# Utility_Micro_v81.net
KiCad netlist of a schematic drawn in EAGLE
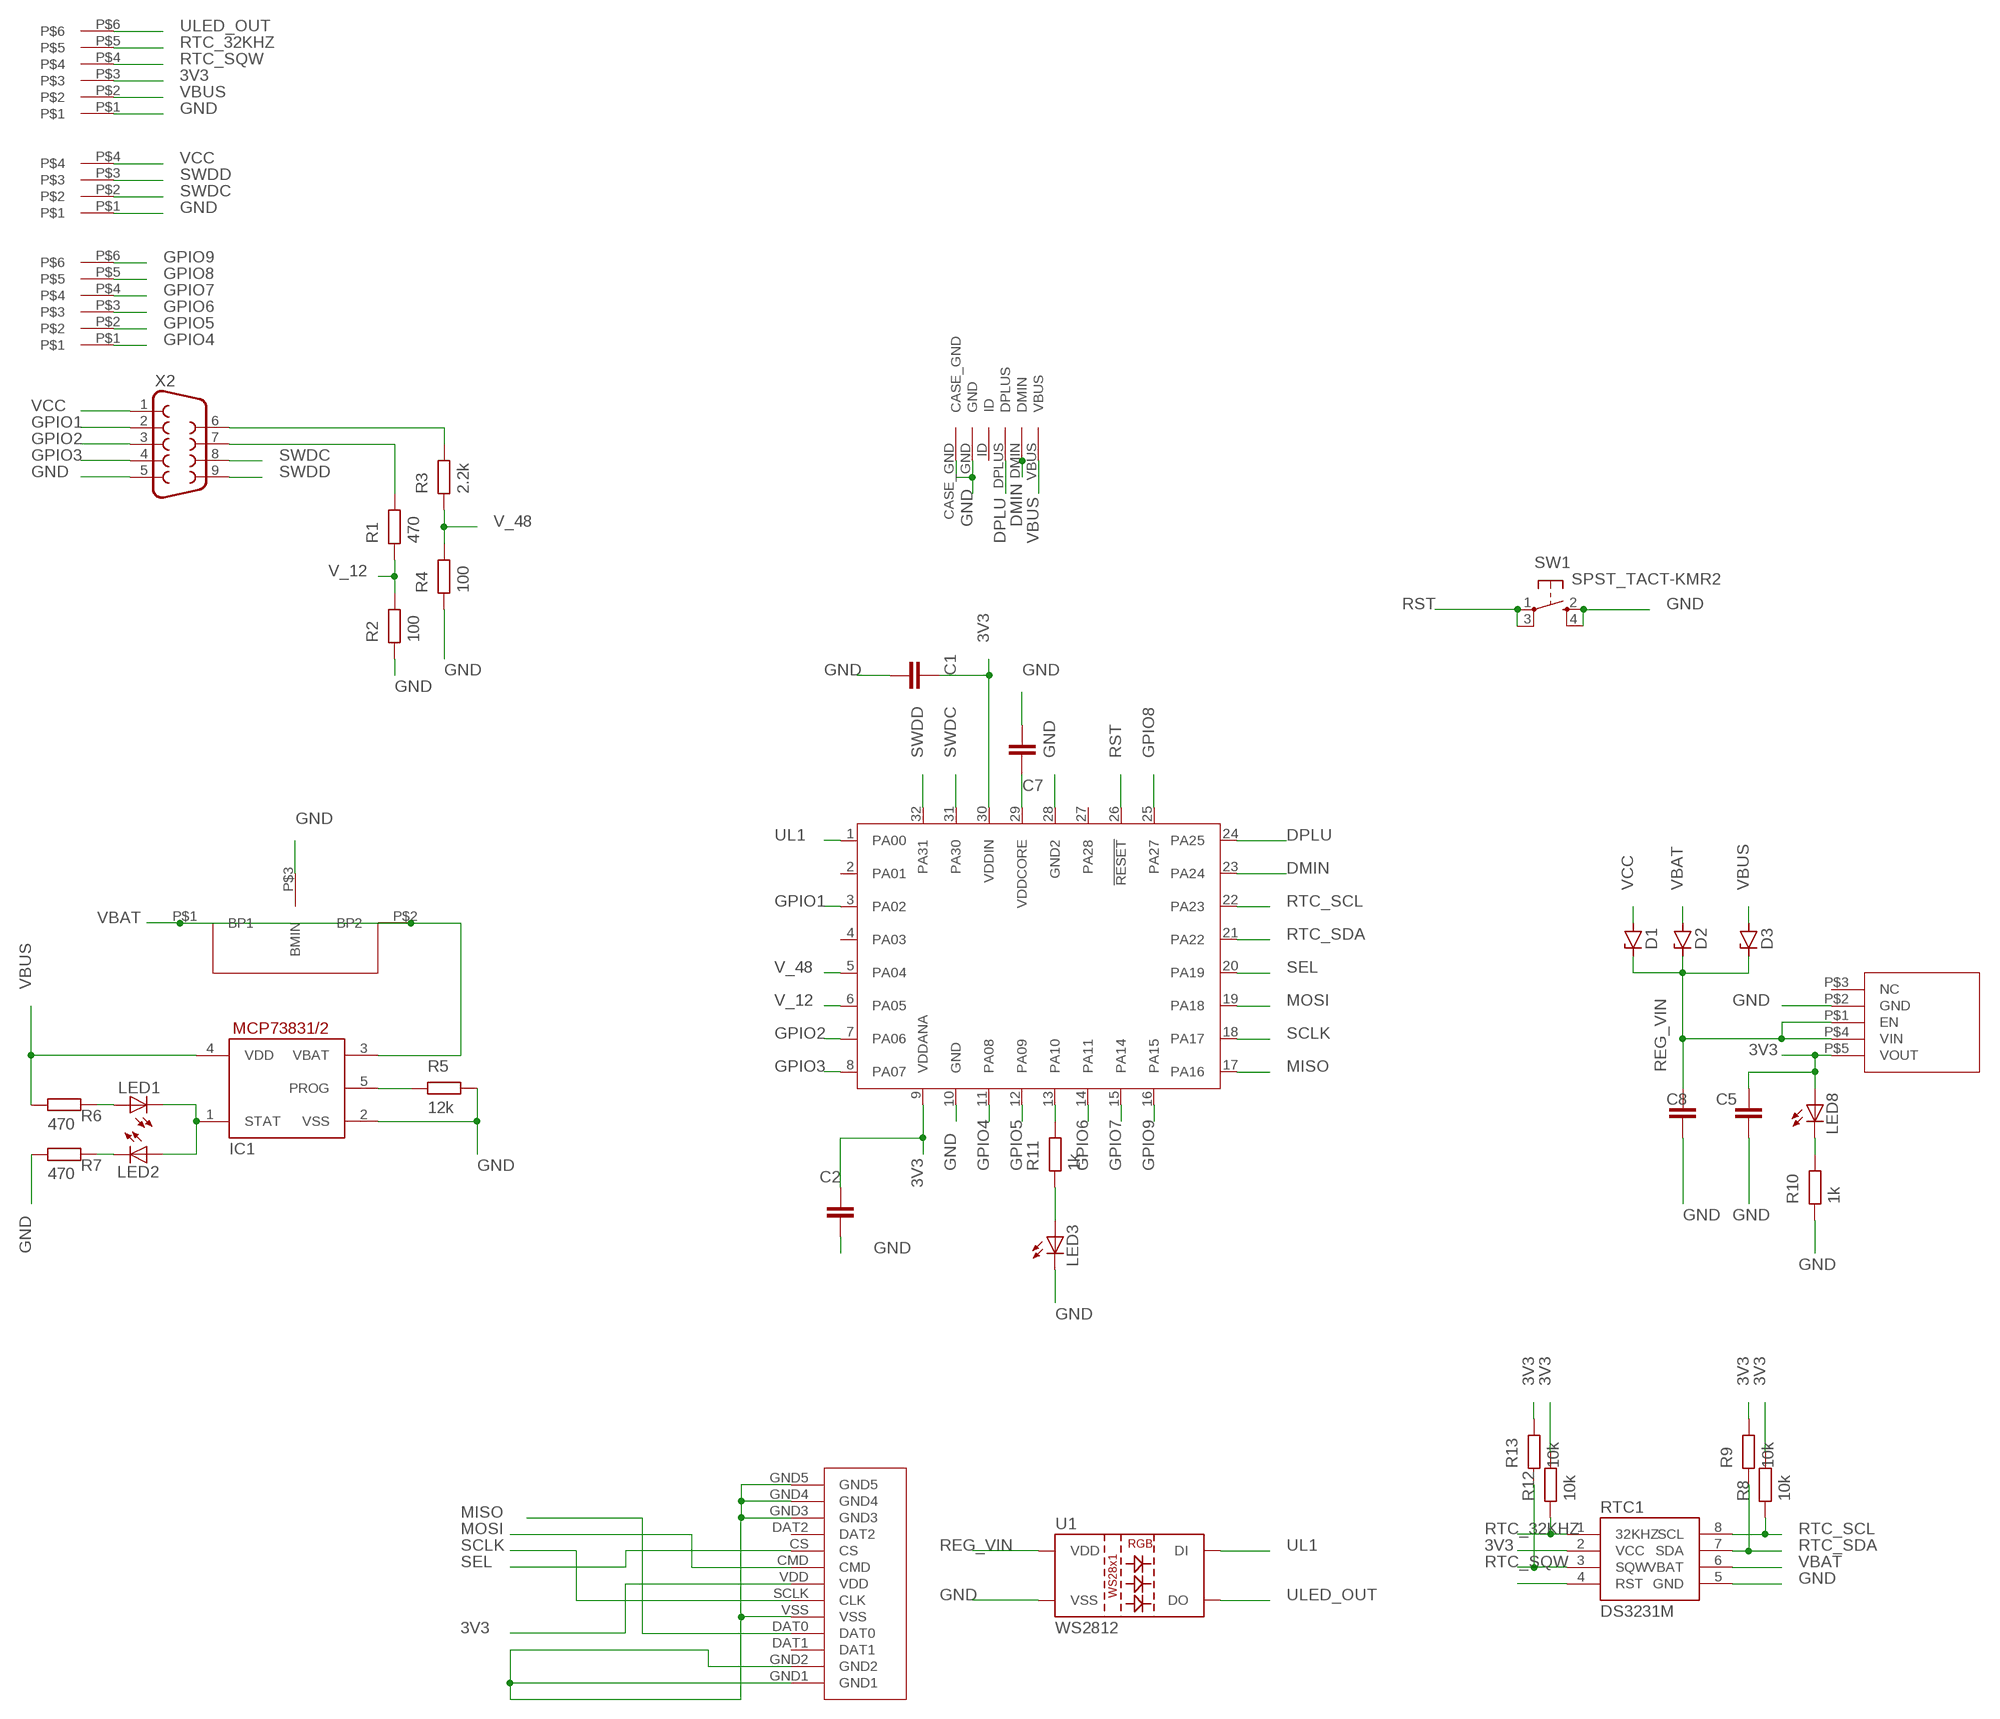
[diagram p0: schematic, sheet 1]

(export (version "E")
  (design (tool "Eeschema 10.0.6"))
  (components
    (comp (ref "ATSAMD21")
      (value "ATSAMD21TQFP")
      (footprint "eagle-import:TQFP32-08")
      (fields (field (name "MANUFACTURER") "Microchip") (field (name "MPN") "ATmega328P"))
      (libsource (lib "eagle-import") (part "ATSAMD21TQFP"))
    )
    (comp (ref "C1")
      (value "100nF")
      (footprint "eagle-import:CAPC1608X85")
      (libsource (lib "eagle-import") (part "CCHIP-0603(1608-METRIC)_"))
    )
    (comp (ref "C2")
      (value "100nF")
      (footprint "eagle-import:CAPC1608X85")
      (libsource (lib "eagle-import") (part "CCHIP-0603(1608-METRIC)_"))
    )
    (comp (ref "C5")
      (value "10uF")
      (footprint "eagle-import:CAPC1608X85")
      (libsource (lib "eagle-import") (part "CCHIP-0603(1608-METRIC)_"))
    )
    (comp (ref "C7")
      (value "1uF")
      (footprint "eagle-import:CAPC1608X85")
      (libsource (lib "eagle-import") (part "CCHIP-0603(1608-METRIC)_"))
    )
    (comp (ref "C8")
      (value "10uF")
      (footprint "eagle-import:CAPC1608X85")
      (libsource (lib "eagle-import") (part "CCHIP-0603(1608-METRIC)_"))
    )
    (comp (ref "D1")
      (value "SCHOTTKY_MBR0520LT1GDO-219-AB(SOD123F)")
      (footprint "eagle-import:SODFL3718X115")
      (fields (field (name "MANUFACTURER") "ON Semiconductor") (field (name "MPN") "MBR0520LT1G"))
      (libsource (lib "eagle-import") (part "SCHOTTKY_DO-219-AB(SOD123F)MBR0520LT1G"))
    )
    (comp (ref "D2")
      (value "SCHOTTKY_MBR0520LT1GDO-219-AB(SOD123F)")
      (footprint "eagle-import:SODFL3718X115")
      (fields (field (name "MANUFACTURER") "ON Semiconductor") (field (name "MPN") "MBR0520LT1G"))
      (libsource (lib "eagle-import") (part "SCHOTTKY_DO-219-AB(SOD123F)MBR0520LT1G"))
    )
    (comp (ref "D3")
      (value "SCHOTTKY_MBR0520LT1GDO-219-AB(SOD123F)")
      (footprint "eagle-import:SODFL3718X115")
      (fields (field (name "MANUFACTURER") "ON Semiconductor") (field (name "MPN") "MBR0520LT1G"))
      (libsource (lib "eagle-import") (part "SCHOTTKY_DO-219-AB(SOD123F)MBR0520LT1G"))
    )
    (comp (ref "IC1")
      (value "MCP73831/OT")
      (footprint "eagle-import:SOT23-5L")
      (libsource (lib "eagle-import") (part "MCP73831/OT"))
    )
    (comp (ref "LED1")
      (value "LEDCHIP-LED0603")
      (footprint "eagle-import:CHIP-LED0603")
      (libsource (lib "eagle-import") (part "LEDCHIP-LED0603"))
    )
    (comp (ref "LED2")
      (value "LEDCHIP-LED0603")
      (footprint "eagle-import:CHIP-LED0603")
      (libsource (lib "eagle-import") (part "LEDCHIP-LED0603"))
    )
    (comp (ref "LED3")
      (value "LEDCHIP-LED0603")
      (footprint "eagle-import:CHIP-LED0603")
      (libsource (lib "eagle-import") (part "LEDCHIP-LED0603"))
    )
    (comp (ref "LED8")
      (value "LEDCHIP-LED0603")
      (footprint "eagle-import:CHIP-LED0603")
      (libsource (lib "eagle-import") (part "LEDCHIP-LED0603"))
    )
    (comp (ref "LIR_2450")
      (value "LIR2450H")
      (footprint "eagle-import:BC-2005")
      (libsource (lib "eagle-import") (part "LIR2450H"))
    )
    (comp (ref "R1")
      (value "470")
      (footprint "eagle-import:RESC1608X60")
      (libsource (lib "eagle-import") (part "RCHIP-0603(1608-METRIC)_"))
    )
    (comp (ref "R2")
      (value "100")
      (footprint "eagle-import:RESC1608X60")
      (libsource (lib "eagle-import") (part "RCHIP-0603(1608-METRIC)_"))
    )
    (comp (ref "R3")
      (value "2.2k")
      (footprint "eagle-import:RESC1608X60")
      (libsource (lib "eagle-import") (part "RCHIP-0603(1608-METRIC)_"))
    )
    (comp (ref "R4")
      (value "100")
      (footprint "eagle-import:RESC1608X60")
      (libsource (lib "eagle-import") (part "RCHIP-0603(1608-METRIC)_"))
    )
    (comp (ref "R5")
      (value "12k")
      (footprint "eagle-import:RESC1608X60")
      (libsource (lib "eagle-import") (part "RCHIP-0603(1608-METRIC)_"))
    )
    (comp (ref "R6")
      (value "470")
      (footprint "eagle-import:RESC1608X60")
      (libsource (lib "eagle-import") (part "RCHIP-0603(1608-METRIC)_"))
    )
    (comp (ref "R7")
      (value "470")
      (footprint "eagle-import:RESC1608X60")
      (libsource (lib "eagle-import") (part "RCHIP-0603(1608-METRIC)_"))
    )
    (comp (ref "R8")
      (value "10k")
      (footprint "eagle-import:RESC1608X60")
      (libsource (lib "eagle-import") (part "RCHIP-0603(1608-METRIC)_"))
    )
    (comp (ref "R9")
      (value "10k")
      (footprint "eagle-import:RESC1608X60")
      (libsource (lib "eagle-import") (part "RCHIP-0603(1608-METRIC)_"))
    )
    (comp (ref "R10")
      (value "1k")
      (footprint "eagle-import:RESC1608X60")
      (libsource (lib "eagle-import") (part "RCHIP-0603(1608-METRIC)_"))
    )
    (comp (ref "R11")
      (value "1k")
      (footprint "eagle-import:RESC1608X60")
      (libsource (lib "eagle-import") (part "RCHIP-0603(1608-METRIC)_"))
    )
    (comp (ref "R12")
      (value "10k")
      (footprint "eagle-import:RESC1608X60")
      (libsource (lib "eagle-import") (part "RCHIP-0603(1608-METRIC)_"))
    )
    (comp (ref "R13")
      (value "10k")
      (footprint "eagle-import:RESC1608X60")
      (libsource (lib "eagle-import") (part "RCHIP-0603(1608-METRIC)_"))
    )
    (comp (ref "RTC1")
      (value "DS3231M")
      (footprint "eagle-import:SO08")
      (libsource (lib "eagle-import") (part "DS3231M"))
    )
    (comp (ref "SW1")
      (value "SPST_TACT-KMR2")
      (footprint "eagle-import:KMR2")
      (libsource (lib "eagle-import") (part "SPST_TACT-KMR2"))
    )
    (comp (ref "U$2")
      (value "MOLEX_MICRO_USB")
      (footprint "eagle-import:MOLEX_MICRO_USB")
      (libsource (lib "eagle-import") (part "MOLEX_MICRO_USB"))
    )
    (comp (ref "U$3")
      (value "AP2112")
      (footprint "eagle-import:SOT-25")
      (libsource (lib "eagle-import") (part "AP2112"))
    )
    (comp (ref "U$4")
      (value "TP_SMALL_6_DEVICE")
      (footprint "eagle-import:TP_SMALL_6")
      (libsource (lib "eagle-import") (part "TP_SMALL_6_DEVICE"))
    )
    (comp (ref "U$5")
      (value "TP_SMALL_6_DEVICE")
      (footprint "eagle-import:TP_SMALL_6")
      (libsource (lib "eagle-import") (part "TP_SMALL_6_DEVICE"))
    )
    (comp (ref "U$6")
      (value "SMALL_MICRO_SD")
      (footprint "eagle-import:MICRO_SD_SMALL")
      (libsource (lib "eagle-import") (part "SMALL_MICRO_SD"))
    )
    (comp (ref "U$10")
      (value "TP_SMALL_4_DEVICE")
      (footprint "eagle-import:TP_SMALL_4")
      (libsource (lib "eagle-import") (part "TP_SMALL_4_DEVICE"))
    )
    (comp (ref "U1")
      (value "WS2812")
      (footprint "eagle-import:LED-TRICOLOR-5050-IC")
      (libsource (lib "eagle-import") (part "WS2812{dblquote}"))
    )
    (comp (ref "X2")
      (value "F09D")
      (footprint "eagle-import:F09D")
      (libsource (lib "eagle-import") (part "F09D"))
    )
  )
  (nets
    (net (code "1") (name "/3V3") (class "Default")
      (node (ref "ATSAMD21") (pin "30") (pinfunction "VDDIN_30") (pintype "power_in"))
      (node (ref "ATSAMD21") (pin "9") (pinfunction "VDDANA_9") (pintype "power_in"))
      (node (ref "C1") (pin "2") (pinfunction "2_2") (pintype "passive"))
      (node (ref "C2") (pin "2") (pinfunction "2_2") (pintype "passive"))
      (node (ref "C5") (pin "1") (pinfunction "1_1") (pintype "passive"))
      (node (ref "LED8") (pin "A") (pinfunction "A_A") (pintype "passive"))
      (node (ref "R12") (pin "2") (pinfunction "2_2") (pintype "passive"))
      (node (ref "R13") (pin "2") (pinfunction "2_2") (pintype "passive"))
      (node (ref "R8") (pin "2") (pinfunction "2_2") (pintype "passive"))
      (node (ref "R9") (pin "2") (pinfunction "2_2") (pintype "passive"))
      (node (ref "RTC1") (pin "2") (pinfunction "VCC_2") (pintype "power_in"))
      (node (ref "U$3") (pin "P$5") (pinfunction "VOUT_P$5") (pintype "power_in"))
      (node (ref "U$4") (pin "P$3") (pinfunction "P$3_P$3") (pintype "bidirectional"))
      (node (ref "U$6") (pin "VDD") (pinfunction "VDD_VDD") (pintype "bidirectional"))
    )
    (net (code "2") (name "/DMIN") (class "Default")
      (node (ref "ATSAMD21") (pin "23") (pinfunction "PA24_23") (pintype "bidirectional"))
      (node (ref "U$2") (pin "DMIN") (pinfunction "DMIN_DMIN") (pintype "bidirectional"))
    )
    (net (code "3") (name "/DPLU") (class "Default")
      (node (ref "ATSAMD21") (pin "24") (pinfunction "PA25_24") (pintype "bidirectional"))
      (node (ref "U$2") (pin "DPLUS") (pinfunction "DPLUS_DPLUS") (pintype "bidirectional"))
    )
    (net (code "4") (name "/GND") (class "Default")
      (node (ref "ATSAMD21") (pin "10") (pinfunction "GND_10") (pintype "passive"))
      (node (ref "ATSAMD21") (pin "28") (pinfunction "GND2_28") (pintype "passive"))
      (node (ref "C1") (pin "1") (pinfunction "1_1") (pintype "passive"))
      (node (ref "C2") (pin "1") (pinfunction "1_1") (pintype "passive"))
      (node (ref "C5") (pin "2") (pinfunction "2_2") (pintype "passive"))
      (node (ref "C7") (pin "1") (pinfunction "1_1") (pintype "passive"))
      (node (ref "C8") (pin "2") (pinfunction "2_2") (pintype "passive"))
      (node (ref "IC1") (pin "2") (pinfunction "VSS_2") (pintype "power_in"))
      (node (ref "LED3") (pin "C") (pinfunction "C_C") (pintype "passive"))
      (node (ref "LIR_2450") (pin "P$3") (pinfunction "BMIN_P$3") (pintype "bidirectional"))
      (node (ref "R10") (pin "1") (pinfunction "1_1") (pintype "passive"))
      (node (ref "R2") (pin "1") (pinfunction "1_1") (pintype "passive"))
      (node (ref "R4") (pin "1") (pinfunction "1_1") (pintype "passive"))
      (node (ref "R5") (pin "2") (pinfunction "2_2") (pintype "passive"))
      (node (ref "R7") (pin "1") (pinfunction "1_1") (pintype "passive"))
      (node (ref "RTC1") (pin "5") (pinfunction "GND_5") (pintype "power_in"))
      (node (ref "SW1") (pin "2") (pinfunction "S_2") (pintype "passive"))
      (node (ref "SW1") (pin "4") (pinfunction "S1_4") (pintype "passive"))
      (node (ref "U$10") (pin "P$1") (pinfunction "P$1_P$1") (pintype "bidirectional"))
      (node (ref "U$2") (pin "CASE_GND") (pinfunction "CASE_GND_CASE_GND") (pintype "bidirectional"))
      (node (ref "U$2") (pin "GND") (pinfunction "GND_GND") (pintype "bidirectional"))
      (node (ref "U$3") (pin "P$2") (pinfunction "GND_P$2") (pintype "passive"))
      (node (ref "U$4") (pin "P$1") (pinfunction "P$1_P$1") (pintype "bidirectional"))
      (node (ref "U1") (pin "6") (pinfunction "VSS_6") (pintype "bidirectional"))
      (node (ref "X2") (pin "5") (pinfunction "5_5") (pintype "passive"))
    )
    (net (code "5") (name "/GPIO1") (class "Default")
      (node (ref "ATSAMD21") (pin "3") (pinfunction "PA02_3") (pintype "bidirectional"))
      (node (ref "X2") (pin "2") (pinfunction "2_2") (pintype "passive"))
    )
    (net (code "6") (name "/GPIO2") (class "Default")
      (node (ref "ATSAMD21") (pin "7") (pinfunction "PA06_7") (pintype "bidirectional"))
      (node (ref "X2") (pin "3") (pinfunction "3_3") (pintype "passive"))
    )
    (net (code "7") (name "/GPIO3") (class "Default")
      (node (ref "ATSAMD21") (pin "8") (pinfunction "PA07_8") (pintype "bidirectional"))
      (node (ref "X2") (pin "4") (pinfunction "4_4") (pintype "passive"))
    )
    (net (code "8") (name "/GPIO4") (class "Default")
      (node (ref "ATSAMD21") (pin "11") (pinfunction "PA08_11") (pintype "bidirectional"))
      (node (ref "U$5") (pin "P$1") (pinfunction "P$1_P$1") (pintype "bidirectional"))
    )
    (net (code "9") (name "/GPIO5") (class "Default")
      (node (ref "ATSAMD21") (pin "12") (pinfunction "PA09_12") (pintype "bidirectional"))
      (node (ref "U$5") (pin "P$2") (pinfunction "P$2_P$2") (pintype "bidirectional"))
    )
    (net (code "10") (name "/GPIO6") (class "Default")
      (node (ref "ATSAMD21") (pin "14") (pinfunction "PA11_14") (pintype "bidirectional"))
      (node (ref "U$5") (pin "P$3") (pinfunction "P$3_P$3") (pintype "bidirectional"))
    )
    (net (code "11") (name "/GPIO7") (class "Default")
      (node (ref "ATSAMD21") (pin "15") (pinfunction "PA14_15") (pintype "bidirectional"))
      (node (ref "U$5") (pin "P$4") (pinfunction "P$4_P$4") (pintype "bidirectional"))
    )
    (net (code "12") (name "/GPIO8") (class "Default")
      (node (ref "ATSAMD21") (pin "25") (pinfunction "PA27_25") (pintype "bidirectional"))
      (node (ref "U$5") (pin "P$5") (pinfunction "P$5_P$5") (pintype "bidirectional"))
    )
    (net (code "13") (name "/GPIO9") (class "Default")
      (node (ref "ATSAMD21") (pin "16") (pinfunction "PA15_16") (pintype "bidirectional"))
      (node (ref "U$5") (pin "P$6") (pinfunction "P$6_P$6") (pintype "bidirectional"))
    )
    (net (code "14") (name "/MISO") (class "Default")
      (node (ref "ATSAMD21") (pin "17") (pinfunction "PA16_17") (pintype "bidirectional"))
      (node (ref "U$6") (pin "DAT0") (pinfunction "DAT0_DAT0") (pintype "bidirectional"))
    )
    (net (code "15") (name "/MOSI") (class "Default")
      (node (ref "ATSAMD21") (pin "19") (pinfunction "PA18_19") (pintype "bidirectional"))
      (node (ref "U$6") (pin "CMD") (pinfunction "CMD_CMD") (pintype "bidirectional"))
    )
    (net (code "16") (name "/REG_VIN") (class "Default")
      (node (ref "C8") (pin "1") (pinfunction "1_1") (pintype "passive"))
      (node (ref "D1") (pin "2") (pinfunction "C_2") (pintype "passive"))
      (node (ref "D2") (pin "2") (pinfunction "C_2") (pintype "passive"))
      (node (ref "D3") (pin "2") (pinfunction "C_2") (pintype "passive"))
      (node (ref "U$3") (pin "P$1") (pinfunction "EN_P$1") (pintype "input"))
      (node (ref "U$3") (pin "P$4") (pinfunction "VIN_P$4") (pintype "power_in"))
      (node (ref "U1") (pin "3") (pinfunction "VDD_3") (pintype "bidirectional"))
      (node (ref "U1") (pin "5") (pinfunction "VDD_5") (pintype "bidirectional"))
    )
    (net (code "17") (name "/RST") (class "Default")
      (node (ref "ATSAMD21") (pin "26") (pinfunction "~{RESET}_26") (pintype "bidirectional"))
      (node (ref "SW1") (pin "1") (pinfunction "P_1") (pintype "passive"))
      (node (ref "SW1") (pin "3") (pinfunction "P1_3") (pintype "passive"))
    )
    (net (code "18") (name "/RTC_32KHZ") (class "Default")
      (node (ref "R12") (pin "1") (pinfunction "1_1") (pintype "passive"))
      (node (ref "RTC1") (pin "1") (pinfunction "32KHZ_1") (pintype "output"))
      (node (ref "U$4") (pin "P$5") (pinfunction "P$5_P$5") (pintype "bidirectional"))
    )
    (net (code "19") (name "/RTC_SCL") (class "Default")
      (node (ref "ATSAMD21") (pin "22") (pinfunction "PA23_22") (pintype "bidirectional"))
      (node (ref "R8") (pin "1") (pinfunction "1_1") (pintype "passive"))
      (node (ref "RTC1") (pin "8") (pinfunction "SCL_8") (pintype "bidirectional"))
    )
    (net (code "20") (name "/RTC_SDA") (class "Default")
      (node (ref "ATSAMD21") (pin "21") (pinfunction "PA22_21") (pintype "bidirectional"))
      (node (ref "R9") (pin "1") (pinfunction "1_1") (pintype "passive"))
      (node (ref "RTC1") (pin "7") (pinfunction "SDA_7") (pintype "bidirectional"))
    )
    (net (code "21") (name "/RTC_SQW") (class "Default")
      (node (ref "R13") (pin "1") (pinfunction "1_1") (pintype "passive"))
      (node (ref "RTC1") (pin "3") (pinfunction "SQW_3") (pintype "output"))
      (node (ref "U$4") (pin "P$4") (pinfunction "P$4_P$4") (pintype "bidirectional"))
    )
    (net (code "22") (name "/SCLK") (class "Default")
      (node (ref "ATSAMD21") (pin "18") (pinfunction "PA17_18") (pintype "bidirectional"))
      (node (ref "U$6") (pin "SCLK") (pinfunction "CLK_SCLK") (pintype "bidirectional"))
    )
    (net (code "23") (name "/SEL") (class "Default")
      (node (ref "ATSAMD21") (pin "20") (pinfunction "PA19_20") (pintype "bidirectional"))
      (node (ref "U$6") (pin "CS") (pinfunction "CS_CS") (pintype "bidirectional"))
    )
    (net (code "24") (name "/SWDC") (class "Default")
      (node (ref "ATSAMD21") (pin "31") (pinfunction "PA30_31") (pintype "bidirectional"))
      (node (ref "U$10") (pin "P$2") (pinfunction "P$2_P$2") (pintype "bidirectional"))
      (node (ref "X2") (pin "8") (pinfunction "8_8") (pintype "passive"))
    )
    (net (code "25") (name "/SWDD") (class "Default")
      (node (ref "ATSAMD21") (pin "32") (pinfunction "PA31_32") (pintype "bidirectional"))
      (node (ref "U$10") (pin "P$3") (pinfunction "P$3_P$3") (pintype "bidirectional"))
      (node (ref "X2") (pin "9") (pinfunction "9_9") (pintype "passive"))
    )
    (net (code "26") (name "/UL1") (class "Default")
      (node (ref "ATSAMD21") (pin "1") (pinfunction "PA00_1") (pintype "bidirectional"))
      (node (ref "U1") (pin "2") (pinfunction "DI_2") (pintype "bidirectional"))
    )
    (net (code "27") (name "/ULED_OUT") (class "Default")
      (node (ref "U$4") (pin "P$6") (pinfunction "P$6_P$6") (pintype "bidirectional"))
      (node (ref "U1") (pin "1") (pinfunction "DO_1") (pintype "bidirectional"))
    )
    (net (code "28") (name "/VBAT") (class "Default")
      (node (ref "D2") (pin "1") (pinfunction "A_1") (pintype "passive"))
      (node (ref "IC1") (pin "3") (pinfunction "VBAT_3") (pintype "bidirectional"))
      (node (ref "LIR_2450") (pin "P$1") (pinfunction "BP1_P$1") (pintype "bidirectional"))
      (node (ref "LIR_2450") (pin "P$2") (pinfunction "BP2_P$2") (pintype "bidirectional"))
      (node (ref "RTC1") (pin "6") (pinfunction "VBAT_6") (pintype "power_in"))
    )
    (net (code "29") (name "/VBUS") (class "Default")
      (node (ref "D3") (pin "1") (pinfunction "A_1") (pintype "passive"))
      (node (ref "IC1") (pin "4") (pinfunction "VDD_4") (pintype "power_in"))
      (node (ref "R6") (pin "1") (pinfunction "1_1") (pintype "passive"))
      (node (ref "U$2") (pin "VBUS") (pinfunction "VBUS_VBUS") (pintype "bidirectional"))
      (node (ref "U$4") (pin "P$2") (pinfunction "P$2_P$2") (pintype "bidirectional"))
    )
    (net (code "30") (name "/VCC") (class "Default")
      (node (ref "D1") (pin "1") (pinfunction "A_1") (pintype "passive"))
      (node (ref "U$10") (pin "P$4") (pinfunction "P$4_P$4") (pintype "bidirectional"))
      (node (ref "X2") (pin "1") (pinfunction "1_1") (pintype "passive"))
    )
    (net (code "31") (name "/V_12") (class "Default")
      (node (ref "ATSAMD21") (pin "6") (pinfunction "PA05_6") (pintype "bidirectional"))
      (node (ref "R1") (pin "1") (pinfunction "1_1") (pintype "passive"))
      (node (ref "R2") (pin "2") (pinfunction "2_2") (pintype "passive"))
    )
    (net (code "32") (name "/V_48") (class "Default")
      (node (ref "ATSAMD21") (pin "5") (pinfunction "PA04_5") (pintype "bidirectional"))
      (node (ref "R3") (pin "1") (pinfunction "1_1") (pintype "passive"))
      (node (ref "R4") (pin "2") (pinfunction "2_2") (pintype "passive"))
    )
    (net (code "33") (name "Net-(ATSAMD21-PA10)") (class "Default")
      (node (ref "ATSAMD21") (pin "13") (pinfunction "PA10_13") (pintype "bidirectional"))
      (node (ref "R11") (pin "2") (pinfunction "2_2") (pintype "passive"))
    )
    (net (code "34") (name "Net-(ATSAMD21-VDDCORE)") (class "Default")
      (node (ref "ATSAMD21") (pin "29") (pinfunction "VDDCORE_29") (pintype "power_in"))
      (node (ref "C7") (pin "2") (pinfunction "2_2") (pintype "passive"))
    )
    (net (code "35") (name "Net-(IC1-PROG)") (class "Default")
      (node (ref "IC1") (pin "5") (pinfunction "PROG_5") (pintype "input"))
      (node (ref "R5") (pin "1") (pinfunction "1_1") (pintype "passive"))
    )
    (net (code "36") (name "Net-(IC1-STAT)") (class "Default")
      (node (ref "IC1") (pin "1") (pinfunction "STAT_1") (pintype "output"))
      (node (ref "LED1") (pin "C") (pinfunction "C_C") (pintype "passive"))
      (node (ref "LED2") (pin "A") (pinfunction "A_A") (pintype "passive"))
    )
    (net (code "37") (name "Net-(LED1-PadA)") (class "Default")
      (node (ref "LED1") (pin "A") (pinfunction "A_A") (pintype "passive"))
      (node (ref "R6") (pin "2") (pinfunction "2_2") (pintype "passive"))
    )
    (net (code "38") (name "Net-(LED2-PadC)") (class "Default")
      (node (ref "LED2") (pin "C") (pinfunction "C_C") (pintype "passive"))
      (node (ref "R7") (pin "2") (pinfunction "2_2") (pintype "passive"))
    )
    (net (code "39") (name "Net-(LED3-PadA)") (class "Default")
      (node (ref "LED3") (pin "A") (pinfunction "A_A") (pintype "passive"))
      (node (ref "R11") (pin "1") (pinfunction "1_1") (pintype "passive"))
    )
    (net (code "40") (name "Net-(LED8-PadC)") (class "Default")
      (node (ref "LED8") (pin "C") (pinfunction "C_C") (pintype "passive"))
      (node (ref "R10") (pin "2") (pinfunction "2_2") (pintype "passive"))
    )
    (net (code "41") (name "Net-(R1-Pad2)") (class "Default")
      (node (ref "R1") (pin "2") (pinfunction "2_2") (pintype "passive"))
      (node (ref "X2") (pin "7") (pinfunction "7_7") (pintype "passive"))
    )
    (net (code "42") (name "Net-(R3-Pad2)") (class "Default")
      (node (ref "R3") (pin "2") (pinfunction "2_2") (pintype "passive"))
      (node (ref "X2") (pin "6") (pinfunction "6_6") (pintype "passive"))
    )
    (net (code "43") (name "Net-(U$6-PadGND1)") (class "Default")
      (node (ref "U$6") (pin "GND1") (pinfunction "GND1_GND1") (pintype "bidirectional"))
      (node (ref "U$6") (pin "GND2") (pinfunction "GND2_GND2") (pintype "bidirectional"))
      (node (ref "U$6") (pin "GND3") (pinfunction "GND3_GND3") (pintype "bidirectional"))
      (node (ref "U$6") (pin "GND4") (pinfunction "GND4_GND4") (pintype "bidirectional"))
      (node (ref "U$6") (pin "GND5") (pinfunction "GND5_GND5") (pintype "bidirectional"))
      (node (ref "U$6") (pin "VSS") (pinfunction "VSS_VSS") (pintype "bidirectional"))
    )
    (net (code "44") (name "unconnected-(ATSAMD21-PA01-Pad2)") (class "Default")
      (node (ref "ATSAMD21") (pin "2") (pinfunction "PA01_2") (pintype "bidirectional"))
    )
    (net (code "45") (name "unconnected-(ATSAMD21-PA03-Pad4)") (class "Default")
      (node (ref "ATSAMD21") (pin "4") (pinfunction "PA03_4") (pintype "bidirectional"))
    )
    (net (code "46") (name "unconnected-(ATSAMD21-PA28-Pad27)") (class "Default")
      (node (ref "ATSAMD21") (pin "27") (pinfunction "PA28_27") (pintype "bidirectional"))
    )
    (net (code "47") (name "unconnected-(RTC1-RST-Pad4)") (class "Default")
      (node (ref "RTC1") (pin "4") (pinfunction "RST_4") (pintype "bidirectional"))
    )
    (net (code "48") (name "unconnected-(U$2-PadID)") (class "Default")
      (node (ref "U$2") (pin "ID") (pinfunction "ID_ID") (pintype "bidirectional"))
    )
    (net (code "49") (name "unconnected-(U$3-NC-PadP$3)") (class "Default")
      (node (ref "U$3") (pin "P$3") (pinfunction "NC_P$3") (pintype "no_connect"))
    )
    (net (code "50") (name "unconnected-(U$6-PadDAT1)") (class "Default")
      (node (ref "U$6") (pin "DAT1") (pinfunction "DAT1_DAT1") (pintype "bidirectional"))
    )
    (net (code "51") (name "unconnected-(U$6-PadDAT2)") (class "Default")
      (node (ref "U$6") (pin "DAT2") (pinfunction "DAT2_DAT2") (pintype "bidirectional"))
    )
  )
)
